# SparkFun_RTK_Facet_-_Display_SD_SIM.net
KiCad netlist of a schematic drawn in EAGLE
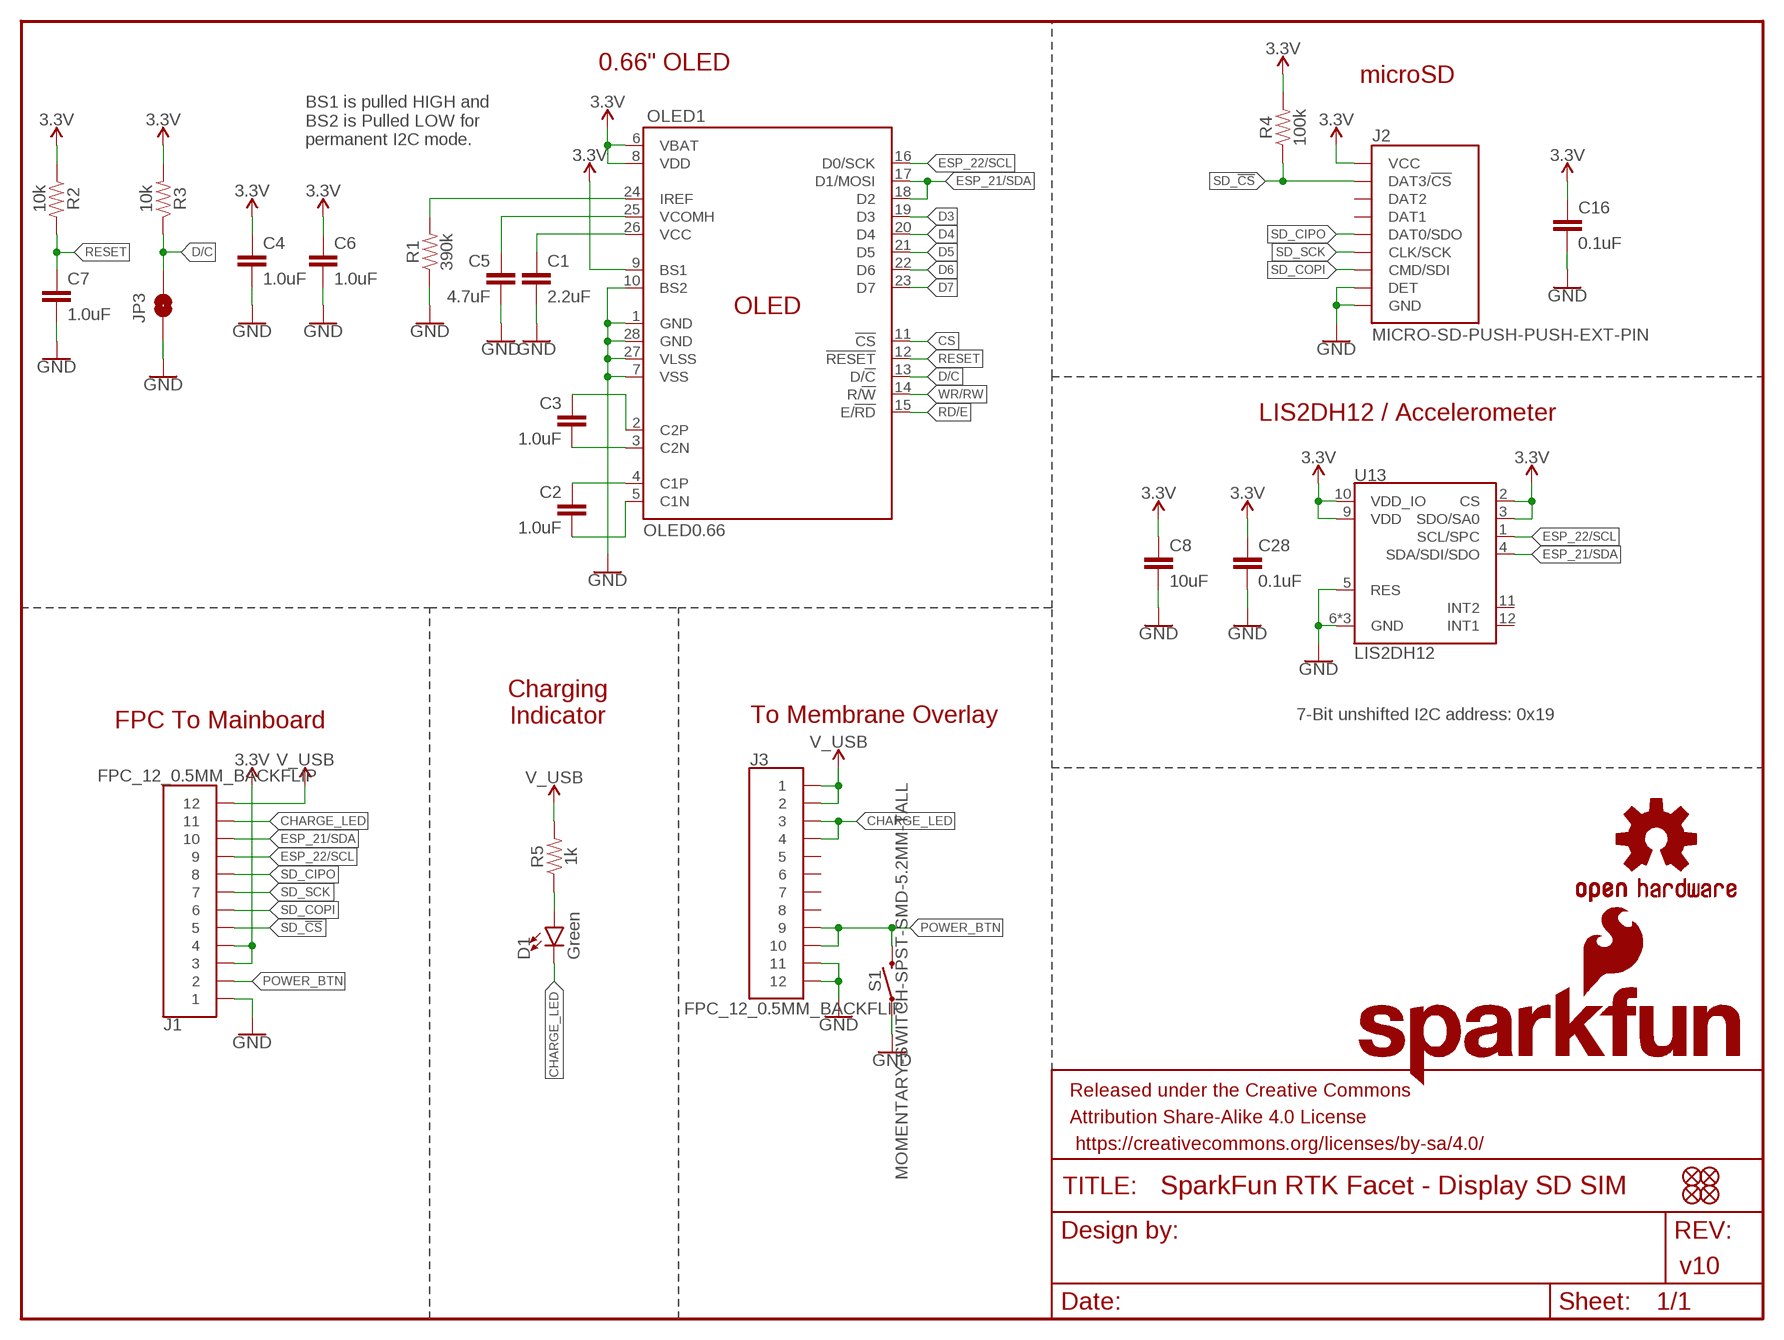
[diagram p0: schematic, sheet 1]

(export (version "E")
  (design (tool "Eeschema 10.0.6"))
  (components
    (comp (ref "C1")
      (value "2.2uF")
      (footprint "eagle-import:0805")
      (libsource (lib "eagle-import") (part "2.2UF-0805-25V-(+80/-20%)"))
    )
    (comp (ref "C2")
      (value "1.0uF")
      (footprint "eagle-import:0805")
      (libsource (lib "eagle-import") (part "1.0UF-0805-25V-10%"))
    )
    (comp (ref "C3")
      (value "1.0uF")
      (footprint "eagle-import:0805")
      (libsource (lib "eagle-import") (part "1.0UF-0805-25V-10%"))
    )
    (comp (ref "C4")
      (value "1.0uF")
      (footprint "eagle-import:0603")
      (libsource (lib "eagle-import") (part "1.0UF-0603-16V-10%"))
    )
    (comp (ref "C5")
      (value "4.7uF")
      (footprint "eagle-import:1206")
      (libsource (lib "eagle-import") (part "4.7UF-1206-16V-(+80/-20%)"))
    )
    (comp (ref "C6")
      (value "1.0uF")
      (footprint "eagle-import:0603")
      (libsource (lib "eagle-import") (part "1.0UF-0603-16V-10%"))
    )
    (comp (ref "C7")
      (value "1.0uF")
      (footprint "eagle-import:0603")
      (libsource (lib "eagle-import") (part "1.0UF-0603-16V-10%"))
    )
    (comp (ref "C8")
      (value "10uF")
      (footprint "eagle-import:0603")
      (libsource (lib "eagle-import") (part "10UF-0603-6.3V-20%"))
    )
    (comp (ref "C16")
      (value "0.1uF")
      (footprint "eagle-import:0603")
      (libsource (lib "eagle-import") (part "0.1UF-0603-25V-(+80/-20%)"))
    )
    (comp (ref "C28")
      (value "0.1uF")
      (footprint "eagle-import:0603")
      (libsource (lib "eagle-import") (part "0.1UF-0603-25V-(+80/-20%)"))
    )
    (comp (ref "D1")
      (value "Green")
      (footprint "eagle-import:LED-1206-BOTTOM")
      (libsource (lib "eagle-import") (part "LED-GREEN1206-BOTTOM"))
    )
    (comp (ref "FID1")
      (value "FIDUCIAL1X2")
      (footprint "eagle-import:FIDUCIAL-1X2")
      (libsource (lib "eagle-import") (part "FIDUCIAL1X2"))
    )
    (comp (ref "FID2")
      (value "FIDUCIAL1X2")
      (footprint "eagle-import:FIDUCIAL-1X2")
      (libsource (lib "eagle-import") (part "FIDUCIAL1X2"))
    )
    (comp (ref "FID3")
      (value "FIDUCIAL1X2")
      (footprint "eagle-import:FIDUCIAL-1X2")
      (libsource (lib "eagle-import") (part "FIDUCIAL1X2"))
    )
    (comp (ref "FID4")
      (value "FIDUCIAL1X2")
      (footprint "eagle-import:FIDUCIAL-1X2")
      (libsource (lib "eagle-import") (part "FIDUCIAL1X2"))
    )
    (comp (ref "FRAME1")
      (value "FRAME-LETTER")
      (footprint "eagle-import:CREATIVE_COMMONS")
      (libsource (lib "eagle-import") (part "FRAME-LETTER"))
    )
    (comp (ref "J1")
      (value "FPC_12_0.5MM_BACKFLIP")
      (footprint "eagle-import:FPC_12_DOUBLESIDED_BACKFLIP")
      (libsource (lib "eagle-import") (part "FPC_12_0.5MM_BACKFLIP"))
    )
    (comp (ref "J2")
      (value "MICRO-SD-PUSH-PUSH-EXT-PIN")
      (footprint "eagle-import:MICROSD-EXTERNALPIN")
      (libsource (lib "eagle-import") (part "MICRO-SD-PUSH-PUSH-EXT-PIN"))
    )
    (comp (ref "J3")
      (value "FPC_12_0.5MM_BACKFLIP")
      (footprint "eagle-import:FPC_12_DOUBLESIDED_BACKFLIP")
      (libsource (lib "eagle-import") (part "FPC_12_0.5MM_BACKFLIP"))
    )
    (comp (ref "JP3")
      (value "JUMPER-SMT_2_NO_SILK")
      (footprint "eagle-import:SMT-JUMPER_2_NO_SILK")
      (libsource (lib "eagle-import") (part "JUMPER-SMT_2_NO_SILK"))
    )
    (comp (ref "LOGO3")
      (value "OSHW-LOGOMINI")
      (footprint "eagle-import:OSHW-LOGO-MINI")
      (libsource (lib "eagle-import") (part "OSHW-LOGOMINI"))
    )
    (comp (ref "LOGO5")
      (value "SFE_LOGO_NAME_FLAME.1_INCH")
      (footprint "eagle-import:SFE_LOGO_NAME_FLAME_.1")
      (libsource (lib "eagle-import") (part "SFE_LOGO_NAME_FLAME.1_INCH"))
    )
    (comp (ref "OLED1")
      (value "OLED0.66")
      (footprint "eagle-import:OLED-0.66-64X48")
      (libsource (lib "eagle-import") (part "OLED0.66"))
    )
    (comp (ref "R1")
      (value "390k")
      (footprint "eagle-import:0603")
      (libsource (lib "eagle-import") (part "390KOHM-0603-1/10W-1%"))
    )
    (comp (ref "R2")
      (value "10k")
      (footprint "eagle-import:0603")
      (libsource (lib "eagle-import") (part "10KOHM-0603-1/10W-1%"))
    )
    (comp (ref "R3")
      (value "10k")
      (footprint "eagle-import:0603")
      (libsource (lib "eagle-import") (part "10KOHM-0603-1/10W-1%"))
    )
    (comp (ref "R4")
      (value "100k")
      (footprint "eagle-import:0603")
      (libsource (lib "eagle-import") (part "100KOHM-0603-1/10W-1%"))
    )
    (comp (ref "R5")
      (value "1k")
      (footprint "eagle-import:0603")
      (libsource (lib "eagle-import") (part "1KOHM-0603-1/10W-1%"))
    )
    (comp (ref "S1")
      (value "MOMENTARY-SWITCH-SPST-SMD-5.2MM-TALL")
      (footprint "eagle-import:TACTILE_SWITCH_SMD_5.2MM")
      (libsource (lib "eagle-import") (part "MOMENTARY-SWITCH-SPST-SMD-5.2MM-TALL"))
    )
    (comp (ref "U13")
      (value "LIS2DH12")
      (footprint "eagle-import:LGA-12-LISDH12")
      (libsource (lib "eagle-import") (part "LIS2DH12"))
    )
  )
  (nets
    (net (code "1") (name "/SD_~{CS}") (class "Default")
      (node (ref "J1") (pin "5") (pinfunction "5_5") (pintype "bidirectional"))
      (node (ref "J2") (pin "2") (pinfunction "DAT3/~{CS}_2") (pintype "bidirectional"))
      (node (ref "R4") (pin "1") (pinfunction "1_1") (pintype "passive"))
    )
    (net (code "2") (name "3.3V") (class "Default")
      (node (ref "C16") (pin "1") (pinfunction "1_1") (pintype "passive"))
      (node (ref "C28") (pin "1") (pinfunction "1_1") (pintype "passive"))
      (node (ref "C4") (pin "1") (pinfunction "1_1") (pintype "passive"))
      (node (ref "C6") (pin "1") (pinfunction "1_1") (pintype "passive"))
      (node (ref "C8") (pin "1") (pinfunction "1_1") (pintype "passive"))
      (node (ref "J1") (pin "3") (pinfunction "3_3") (pintype "bidirectional"))
      (node (ref "J1") (pin "4") (pinfunction "4_4") (pintype "bidirectional"))
      (node (ref "J2") (pin "4") (pinfunction "VCC_4") (pintype "bidirectional"))
      (node (ref "OLED1") (pin "6") (pinfunction "VBAT_6") (pintype "bidirectional"))
      (node (ref "OLED1") (pin "8") (pinfunction "VDD_8") (pintype "bidirectional"))
      (node (ref "OLED1") (pin "9") (pinfunction "BS1_9") (pintype "bidirectional"))
      (node (ref "R2") (pin "1") (pinfunction "1_1") (pintype "passive"))
      (node (ref "R3") (pin "2") (pinfunction "2_2") (pintype "passive"))
      (node (ref "R4") (pin "2") (pinfunction "2_2") (pintype "passive"))
      (node (ref "U13") (pin "10") (pinfunction "VDD_IO_10") (pintype "bidirectional"))
      (node (ref "U13") (pin "2") (pinfunction "CS_2") (pintype "bidirectional"))
      (node (ref "U13") (pin "3") (pinfunction "SDO/SA0_3") (pintype "bidirectional"))
      (node (ref "U13") (pin "9") (pinfunction "VDD_9") (pintype "bidirectional"))
    )
    (net (code "3") (name "CHARGE_LED") (class "Default")
      (node (ref "D1") (pin "C") (pinfunction "C_C") (pintype "passive"))
      (node (ref "J1") (pin "11") (pinfunction "11_11") (pintype "bidirectional"))
      (node (ref "J3") (pin "3") (pinfunction "3_3") (pintype "bidirectional"))
      (node (ref "J3") (pin "4") (pinfunction "4_4") (pintype "bidirectional"))
    )
    (net (code "4") (name "CS") (class "Default")
      (node (ref "OLED1") (pin "11") (pinfunction "~{CS}_11") (pintype "bidirectional"))
    )
    (net (code "5") (name "D3") (class "Default")
      (node (ref "OLED1") (pin "19") (pinfunction "D3_19") (pintype "bidirectional"))
    )
    (net (code "6") (name "D4") (class "Default")
      (node (ref "OLED1") (pin "20") (pinfunction "D4_20") (pintype "bidirectional"))
    )
    (net (code "7") (name "D5") (class "Default")
      (node (ref "OLED1") (pin "21") (pinfunction "D5_21") (pintype "bidirectional"))
    )
    (net (code "8") (name "D6") (class "Default")
      (node (ref "OLED1") (pin "22") (pinfunction "D6_22") (pintype "bidirectional"))
    )
    (net (code "9") (name "D7") (class "Default")
      (node (ref "OLED1") (pin "23") (pinfunction "D7_23") (pintype "bidirectional"))
    )
    (net (code "10") (name "D{slash}C") (class "Default")
      (node (ref "JP3") (pin "2") (pinfunction "2_2") (pintype "passive"))
      (node (ref "OLED1") (pin "13") (pinfunction "D/~{C}_13") (pintype "bidirectional"))
      (node (ref "R3") (pin "1") (pinfunction "1_1") (pintype "passive"))
    )
    (net (code "11") (name "ESP_21{slash}SDA") (class "Default")
      (node (ref "J1") (pin "10") (pinfunction "10_10") (pintype "bidirectional"))
      (node (ref "OLED1") (pin "17") (pinfunction "D1/MOSI_17") (pintype "bidirectional"))
      (node (ref "OLED1") (pin "18") (pinfunction "D2_18") (pintype "bidirectional"))
      (node (ref "U13") (pin "4") (pinfunction "SDA/SDI/SDO_4") (pintype "bidirectional"))
    )
    (net (code "12") (name "ESP_22{slash}SCL") (class "Default")
      (node (ref "J1") (pin "9") (pinfunction "9_9") (pintype "bidirectional"))
      (node (ref "OLED1") (pin "16") (pinfunction "D0/SCK_16") (pintype "bidirectional"))
      (node (ref "U13") (pin "1") (pinfunction "SCL/SPC_1") (pintype "bidirectional"))
    )
    (net (code "13") (name "GND") (class "Default")
      (node (ref "C1") (pin "2") (pinfunction "2_2") (pintype "passive"))
      (node (ref "C16") (pin "2") (pinfunction "2_2") (pintype "passive"))
      (node (ref "C28") (pin "2") (pinfunction "2_2") (pintype "passive"))
      (node (ref "C4") (pin "2") (pinfunction "2_2") (pintype "passive"))
      (node (ref "C5") (pin "2") (pinfunction "2_2") (pintype "passive"))
      (node (ref "C6") (pin "2") (pinfunction "2_2") (pintype "passive"))
      (node (ref "C7") (pin "2") (pinfunction "2_2") (pintype "passive"))
      (node (ref "C8") (pin "2") (pinfunction "2_2") (pintype "passive"))
      (node (ref "J1") (pin "1") (pinfunction "1_1") (pintype "bidirectional"))
      (node (ref "J2") (pin "10") (pinfunction "GND_10") (pintype "bidirectional"))
      (node (ref "J2") (pin "11") (pinfunction "GND_11") (pintype "bidirectional"))
      (node (ref "J2") (pin "12") (pinfunction "GND_12") (pintype "bidirectional"))
      (node (ref "J2") (pin "13") (pinfunction "GND_13") (pintype "bidirectional"))
      (node (ref "J2") (pin "6") (pinfunction "GND_6") (pintype "bidirectional"))
      (node (ref "J2") (pin "9") (pinfunction "DET_9") (pintype "bidirectional"))
      (node (ref "J3") (pin "11") (pinfunction "11_11") (pintype "bidirectional"))
      (node (ref "J3") (pin "12") (pinfunction "12_12") (pintype "bidirectional"))
      (node (ref "JP3") (pin "1") (pinfunction "1_1") (pintype "passive"))
      (node (ref "OLED1") (pin "1") (pinfunction "GND_1") (pintype "bidirectional"))
      (node (ref "OLED1") (pin "10") (pinfunction "BS2_10") (pintype "bidirectional"))
      (node (ref "OLED1") (pin "27") (pinfunction "VLSS_27") (pintype "bidirectional"))
      (node (ref "OLED1") (pin "28") (pinfunction "GND_28") (pintype "bidirectional"))
      (node (ref "OLED1") (pin "7") (pinfunction "VSS_7") (pintype "bidirectional"))
      (node (ref "R1") (pin "1") (pinfunction "1_1") (pintype "passive"))
      (node (ref "S1") (pin "1") (pinfunction "1_1") (pintype "passive"))
      (node (ref "U13") (pin "5") (pinfunction "RES_5") (pintype "bidirectional"))
      (node (ref "U13") (pin "6") (pinfunction "GND_6") (pintype "bidirectional"))
      (node (ref "U13") (pin "7") (pinfunction "GND_7") (pintype "bidirectional"))
      (node (ref "U13") (pin "8") (pinfunction "GND_8") (pintype "bidirectional"))
    )
    (net (code "14") (name "Net-(D1-PadA)") (class "Default")
      (node (ref "D1") (pin "A") (pinfunction "A_A") (pintype "passive"))
      (node (ref "R5") (pin "1") (pinfunction "1_1") (pintype "passive"))
    )
    (net (code "15") (name "Net-(OLED1-C1N)") (class "Default")
      (node (ref "C2") (pin "2") (pinfunction "2_2") (pintype "passive"))
      (node (ref "OLED1") (pin "5") (pinfunction "C1N_5") (pintype "bidirectional"))
    )
    (net (code "16") (name "Net-(OLED1-C1P)") (class "Default")
      (node (ref "C2") (pin "1") (pinfunction "1_1") (pintype "passive"))
      (node (ref "OLED1") (pin "4") (pinfunction "C1P_4") (pintype "bidirectional"))
    )
    (net (code "17") (name "Net-(OLED1-C2N)") (class "Default")
      (node (ref "C3") (pin "2") (pinfunction "2_2") (pintype "passive"))
      (node (ref "OLED1") (pin "3") (pinfunction "C2N_3") (pintype "bidirectional"))
    )
    (net (code "18") (name "Net-(OLED1-C2P)") (class "Default")
      (node (ref "C3") (pin "1") (pinfunction "1_1") (pintype "passive"))
      (node (ref "OLED1") (pin "2") (pinfunction "C2P_2") (pintype "bidirectional"))
    )
    (net (code "19") (name "Net-(OLED1-IREF)") (class "Default")
      (node (ref "OLED1") (pin "24") (pinfunction "IREF_24") (pintype "bidirectional"))
      (node (ref "R1") (pin "2") (pinfunction "2_2") (pintype "passive"))
    )
    (net (code "20") (name "Net-(OLED1-VCC)") (class "Default")
      (node (ref "C1") (pin "1") (pinfunction "1_1") (pintype "passive"))
      (node (ref "OLED1") (pin "26") (pinfunction "VCC_26") (pintype "bidirectional"))
    )
    (net (code "21") (name "Net-(OLED1-VCOMH)") (class "Default")
      (node (ref "C5") (pin "1") (pinfunction "1_1") (pintype "passive"))
      (node (ref "OLED1") (pin "25") (pinfunction "VCOMH_25") (pintype "bidirectional"))
    )
    (net (code "22") (name "POWER_BTN") (class "Default")
      (node (ref "J1") (pin "2") (pinfunction "2_2") (pintype "bidirectional"))
      (node (ref "J3") (pin "10") (pinfunction "10_10") (pintype "bidirectional"))
      (node (ref "J3") (pin "9") (pinfunction "9_9") (pintype "bidirectional"))
      (node (ref "S1") (pin "3") (pinfunction "2_3") (pintype "passive"))
    )
    (net (code "23") (name "RD{slash}E") (class "Default")
      (node (ref "OLED1") (pin "15") (pinfunction "E/~{RD}_15") (pintype "bidirectional"))
    )
    (net (code "24") (name "RESET") (class "Default")
      (node (ref "C7") (pin "1") (pinfunction "1_1") (pintype "passive"))
      (node (ref "OLED1") (pin "12") (pinfunction "~{RESET}_12") (pintype "bidirectional"))
      (node (ref "R2") (pin "2") (pinfunction "2_2") (pintype "passive"))
    )
    (net (code "25") (name "SD_CIPO") (class "Default")
      (node (ref "J1") (pin "8") (pinfunction "8_8") (pintype "bidirectional"))
      (node (ref "J2") (pin "7") (pinfunction "DAT0/SDO_7") (pintype "bidirectional"))
    )
    (net (code "26") (name "SD_COPI") (class "Default")
      (node (ref "J1") (pin "6") (pinfunction "6_6") (pintype "bidirectional"))
      (node (ref "J2") (pin "3") (pinfunction "CMD/SDI_3") (pintype "bidirectional"))
    )
    (net (code "27") (name "SD_SCK") (class "Default")
      (node (ref "J1") (pin "7") (pinfunction "7_7") (pintype "bidirectional"))
      (node (ref "J2") (pin "5") (pinfunction "CLK/SCK_5") (pintype "bidirectional"))
    )
    (net (code "28") (name "V_USB") (class "Default")
      (node (ref "J1") (pin "12") (pinfunction "12_12") (pintype "bidirectional"))
      (node (ref "J3") (pin "1") (pinfunction "1_1") (pintype "bidirectional"))
      (node (ref "J3") (pin "2") (pinfunction "2_2") (pintype "bidirectional"))
      (node (ref "R5") (pin "2") (pinfunction "2_2") (pintype "passive"))
    )
    (net (code "29") (name "WR{slash}RW") (class "Default")
      (node (ref "OLED1") (pin "14") (pinfunction "R/~{W}_14") (pintype "bidirectional"))
    )
    (net (code "30") (name "unconnected-(J2-DAT1-Pad8)") (class "Default")
      (node (ref "J2") (pin "8") (pinfunction "DAT1_8") (pintype "bidirectional"))
    )
    (net (code "31") (name "unconnected-(J2-DAT2-Pad1)") (class "Default")
      (node (ref "J2") (pin "1") (pinfunction "DAT2_1") (pintype "bidirectional"))
    )
    (net (code "32") (name "unconnected-(J3-Pad5)") (class "Default")
      (node (ref "J3") (pin "5") (pinfunction "5_5") (pintype "bidirectional"))
    )
    (net (code "33") (name "unconnected-(J3-Pad6)") (class "Default")
      (node (ref "J3") (pin "6") (pinfunction "6_6") (pintype "bidirectional"))
    )
    (net (code "34") (name "unconnected-(J3-Pad7)") (class "Default")
      (node (ref "J3") (pin "7") (pinfunction "7_7") (pintype "bidirectional"))
    )
    (net (code "35") (name "unconnected-(J3-Pad8)") (class "Default")
      (node (ref "J3") (pin "8") (pinfunction "8_8") (pintype "bidirectional"))
    )
    (net (code "36") (name "unconnected-(U13-INT1-Pad12)") (class "Default")
      (node (ref "U13") (pin "12") (pinfunction "INT1_12") (pintype "bidirectional"))
    )
    (net (code "37") (name "unconnected-(U13-INT2-Pad11)") (class "Default")
      (node (ref "U13") (pin "11") (pinfunction "INT2_11") (pintype "bidirectional"))
    )
  )
)
